# I2C-dluga-linia.net
KiCad netlist of a schematic drawn in EAGLE
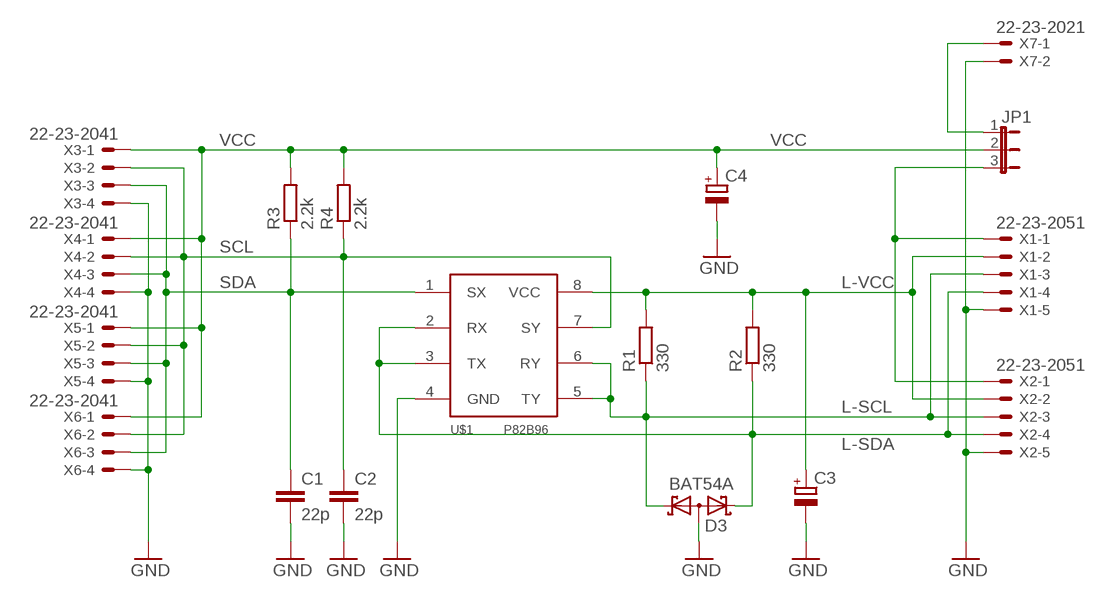
[diagram p0: schematic, sheet 1]

(export (version "E")
  (design (tool "Eeschema 10.0.6"))
  (components
    (comp (ref "C1")
      (value "22p")
      (footprint "eagle-import:C1206")
      (libsource (lib "eagle-import") (part "C-EUC1206"))
    )
    (comp (ref "C2")
      (value "22p")
      (footprint "eagle-import:C1206")
      (libsource (lib "eagle-import") (part "C-EUC1206"))
    )
    (comp (ref "C3")
      (value "CPOL-EUE5-10.5")
      (footprint "eagle-import:E5-10,5")
      (libsource (lib "eagle-import") (part "CPOL-EUE5-10.5"))
    )
    (comp (ref "C4")
      (value "CPOL-EUE3.5-8")
      (footprint "eagle-import:E3,5-8")
      (libsource (lib "eagle-import") (part "CPOL-EUE3.5-8"))
    )
    (comp (ref "D3")
      (value "BAT54A")
      (footprint "eagle-import:SOT23")
      (libsource (lib "eagle-import") (part "BAT54A"))
    )
    (comp (ref "JP1")
      (value "JP2E")
      (footprint "eagle-import:JP2")
      (libsource (lib "eagle-import") (part "JP2E"))
    )
    (comp (ref "R1")
      (value "330")
      (footprint "eagle-import:R1206")
      (libsource (lib "eagle-import") (part "R-EU_R1206"))
    )
    (comp (ref "R2")
      (value "330")
      (footprint "eagle-import:R1206")
      (libsource (lib "eagle-import") (part "R-EU_R1206"))
    )
    (comp (ref "R3")
      (value "2.2k")
      (footprint "eagle-import:R1206")
      (libsource (lib "eagle-import") (part "R-EU_R1206"))
    )
    (comp (ref "R4")
      (value "2.2k")
      (footprint "eagle-import:R1206")
      (libsource (lib "eagle-import") (part "R-EU_R1206"))
    )
    (comp (ref "U$1")
      (value "P82B96")
      (footprint "eagle-import:SOIC8")
      (libsource (lib "eagle-import") (part "P82B96"))
    )
    (comp (ref "X1")
      (value "22-23-2051")
      (footprint "eagle-import:22-23-2051")
      (fields (field (name "MF") "MOLEX"))
      (libsource (lib "eagle-import") (part "22-23-2051"))
    )
    (comp (ref "X2")
      (value "22-23-2051")
      (footprint "eagle-import:22-23-2051")
      (fields (field (name "MF") "MOLEX"))
      (libsource (lib "eagle-import") (part "22-23-2051"))
    )
    (comp (ref "X3")
      (value "22-23-2041")
      (footprint "eagle-import:22-23-2041")
      (fields (field (name "MF") "MOLEX"))
      (libsource (lib "eagle-import") (part "22-23-2041"))
    )
    (comp (ref "X4")
      (value "22-23-2041")
      (footprint "eagle-import:22-23-2041")
      (fields (field (name "MF") "MOLEX"))
      (libsource (lib "eagle-import") (part "22-23-2041"))
    )
    (comp (ref "X5")
      (value "22-23-2041")
      (footprint "eagle-import:22-23-2041")
      (fields (field (name "MF") "MOLEX"))
      (libsource (lib "eagle-import") (part "22-23-2041"))
    )
    (comp (ref "X6")
      (value "22-23-2041")
      (footprint "eagle-import:22-23-2041")
      (fields (field (name "MF") "MOLEX"))
      (libsource (lib "eagle-import") (part "22-23-2041"))
    )
    (comp (ref "X7")
      (value "22-23-2021")
      (footprint "eagle-import:22-23-2021")
      (fields (field (name "MF") "MOLEX"))
      (libsource (lib "eagle-import") (part "22-23-2021"))
    )
  )
  (nets
    (net (code "1") (name "/L-SCL") (class "Default")
      (node (ref "D3") (pin "1") (pinfunction "K1_1") (pintype "passive"))
      (node (ref "R1") (pin "1") (pinfunction "1_1") (pintype "passive"))
      (node (ref "U$1") (pin "5") (pinfunction "TY_5") (pintype "bidirectional"))
      (node (ref "U$1") (pin "6") (pinfunction "RY_6") (pintype "bidirectional"))
      (node (ref "X1") (pin "3") (pinfunction "S_3") (pintype "passive"))
      (node (ref "X2") (pin "3") (pinfunction "S_3") (pintype "passive"))
    )
    (net (code "2") (name "/L-SDA") (class "Default")
      (node (ref "D3") (pin "2") (pinfunction "K2_2") (pintype "passive"))
      (node (ref "R2") (pin "1") (pinfunction "1_1") (pintype "passive"))
      (node (ref "U$1") (pin "2") (pinfunction "RX_2") (pintype "bidirectional"))
      (node (ref "U$1") (pin "3") (pinfunction "TX_3") (pintype "bidirectional"))
      (node (ref "X1") (pin "4") (pinfunction "S_4") (pintype "passive"))
      (node (ref "X2") (pin "4") (pinfunction "S_4") (pintype "passive"))
    )
    (net (code "3") (name "/L-VCC") (class "Default")
      (node (ref "C3") (pin "+") (pinfunction "+_+") (pintype "passive"))
      (node (ref "R1") (pin "2") (pinfunction "2_2") (pintype "passive"))
      (node (ref "R2") (pin "2") (pinfunction "2_2") (pintype "passive"))
      (node (ref "U$1") (pin "8") (pinfunction "VCC_8") (pintype "bidirectional"))
      (node (ref "X1") (pin "2") (pinfunction "S_2") (pintype "passive"))
      (node (ref "X2") (pin "2") (pinfunction "S_2") (pintype "passive"))
    )
    (net (code "4") (name "/SCL") (class "Default")
      (node (ref "C2") (pin "1") (pinfunction "1_1") (pintype "passive"))
      (node (ref "R4") (pin "1") (pinfunction "1_1") (pintype "passive"))
      (node (ref "U$1") (pin "7") (pinfunction "SY_7") (pintype "bidirectional"))
      (node (ref "X3") (pin "2") (pinfunction "S_2") (pintype "passive"))
      (node (ref "X4") (pin "2") (pinfunction "S_2") (pintype "passive"))
      (node (ref "X5") (pin "2") (pinfunction "S_2") (pintype "passive"))
      (node (ref "X6") (pin "2") (pinfunction "S_2") (pintype "passive"))
    )
    (net (code "5") (name "/SDA") (class "Default")
      (node (ref "C1") (pin "1") (pinfunction "1_1") (pintype "passive"))
      (node (ref "R3") (pin "1") (pinfunction "1_1") (pintype "passive"))
      (node (ref "U$1") (pin "1") (pinfunction "SX_1") (pintype "bidirectional"))
      (node (ref "X3") (pin "3") (pinfunction "S_3") (pintype "passive"))
      (node (ref "X4") (pin "3") (pinfunction "S_3") (pintype "passive"))
      (node (ref "X5") (pin "3") (pinfunction "S_3") (pintype "passive"))
      (node (ref "X6") (pin "3") (pinfunction "S_3") (pintype "passive"))
    )
    (net (code "6") (name "/VCC") (class "Default")
      (node (ref "C4") (pin "+") (pinfunction "+_+") (pintype "passive"))
      (node (ref "JP1") (pin "2") (pinfunction "2_2") (pintype "passive"))
      (node (ref "R3") (pin "2") (pinfunction "2_2") (pintype "passive"))
      (node (ref "R4") (pin "2") (pinfunction "2_2") (pintype "passive"))
      (node (ref "X3") (pin "1") (pinfunction "S_1") (pintype "passive"))
      (node (ref "X4") (pin "1") (pinfunction "S_1") (pintype "passive"))
      (node (ref "X5") (pin "1") (pinfunction "S_1") (pintype "passive"))
      (node (ref "X6") (pin "1") (pinfunction "S_1") (pintype "passive"))
    )
    (net (code "7") (name "GND") (class "Default")
      (node (ref "C1") (pin "2") (pinfunction "2_2") (pintype "passive"))
      (node (ref "C2") (pin "2") (pinfunction "2_2") (pintype "passive"))
      (node (ref "C3") (pin "-") (pinfunction "-_-") (pintype "passive"))
      (node (ref "C4") (pin "-") (pinfunction "-_-") (pintype "passive"))
      (node (ref "D3") (pin "3") (pinfunction "AA_3") (pintype "passive"))
      (node (ref "U$1") (pin "4") (pinfunction "GND_4") (pintype "bidirectional"))
      (node (ref "X1") (pin "5") (pinfunction "S_5") (pintype "passive"))
      (node (ref "X2") (pin "5") (pinfunction "S_5") (pintype "passive"))
      (node (ref "X3") (pin "4") (pinfunction "S_4") (pintype "passive"))
      (node (ref "X4") (pin "4") (pinfunction "S_4") (pintype "passive"))
      (node (ref "X5") (pin "4") (pinfunction "S_4") (pintype "passive"))
      (node (ref "X6") (pin "4") (pinfunction "S_4") (pintype "passive"))
      (node (ref "X7") (pin "2") (pinfunction "S_2") (pintype "passive"))
    )
    (net (code "8") (name "Net-(X1A-S)") (class "Default")
      (node (ref "JP1") (pin "3") (pinfunction "3_3") (pintype "passive"))
      (node (ref "X1") (pin "1") (pinfunction "S_1") (pintype "passive"))
      (node (ref "X2") (pin "1") (pinfunction "S_1") (pintype "passive"))
    )
    (net (code "9") (name "Net-(X7A-S)") (class "Default")
      (node (ref "JP1") (pin "1") (pinfunction "1_1") (pintype "passive"))
      (node (ref "X7") (pin "1") (pinfunction "S_1") (pintype "passive"))
    )
  )
)
